# V2.net
KiCad netlist of a schematic drawn in EAGLE
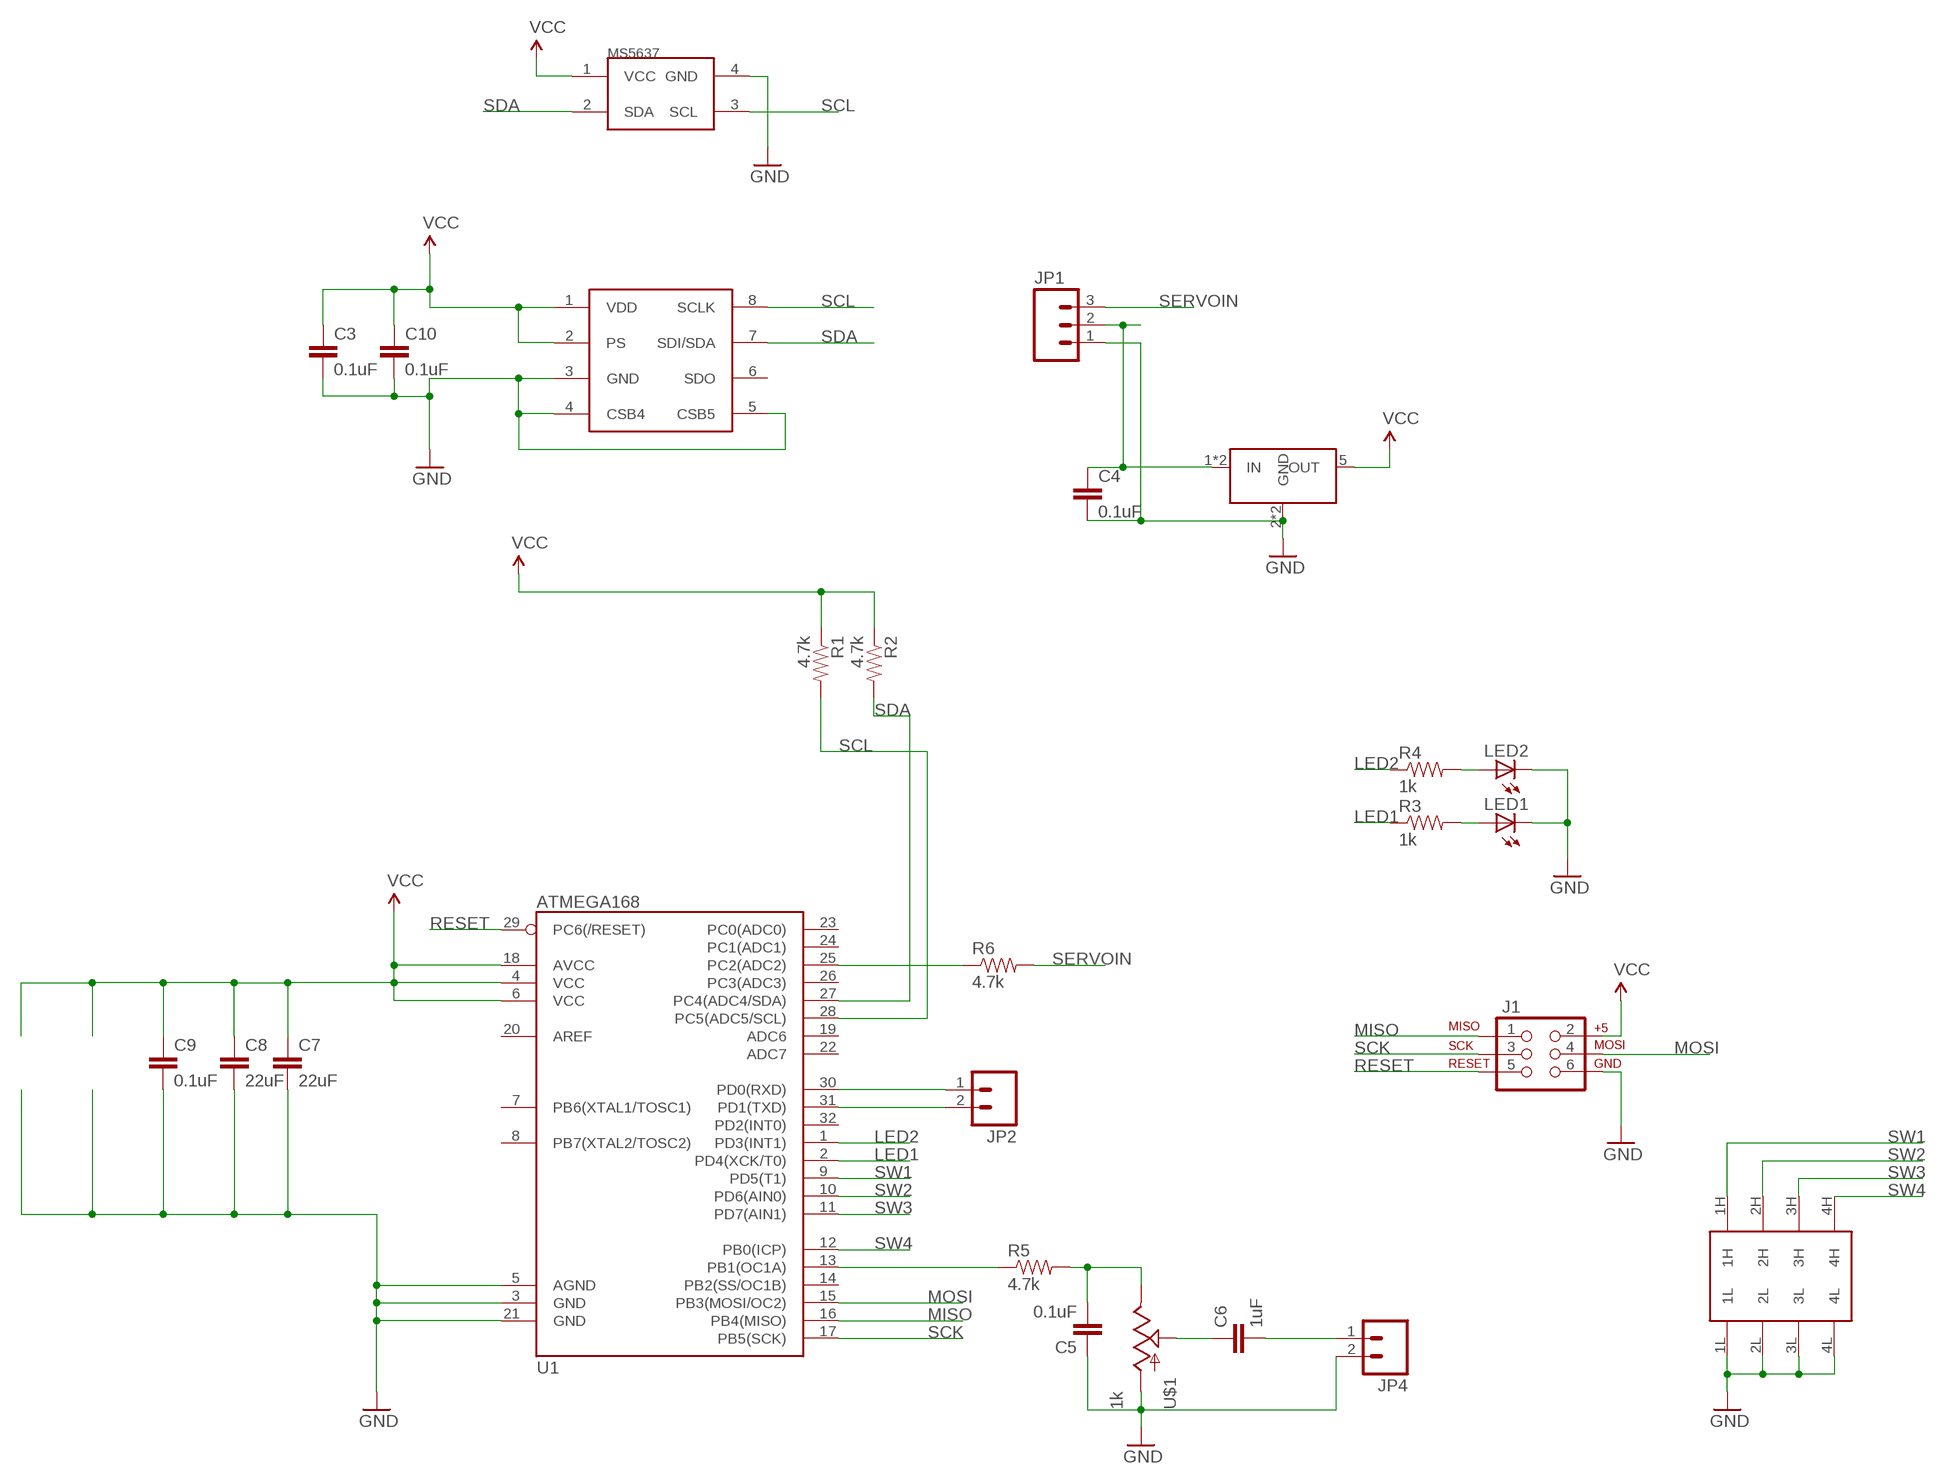
[diagram p0: schematic, sheet 1]

(export (version "E")
  (design (tool "Eeschema 10.0.6"))
  (components
    (comp (ref "C3")
      (value "0.1uF")
      (footprint "eagle-import:0603-CAP")
      (libsource (lib "eagle-import") (part "CAP0603-CAP"))
    )
    (comp (ref "C4")
      (value "0.1uF")
      (footprint "eagle-import:0603-CAP")
      (libsource (lib "eagle-import") (part "CAP0603-CAP"))
    )
    (comp (ref "C5")
      (value "0.1uF")
      (footprint "eagle-import:0603-CAP")
      (libsource (lib "eagle-import") (part "CAP0603-CAP"))
    )
    (comp (ref "C6")
      (value "1uF")
      (footprint "eagle-import:0603-CAP")
      (libsource (lib "eagle-import") (part "CAP0603-CAP"))
    )
    (comp (ref "C7")
      (value "22uF")
      (footprint "eagle-import:0805")
      (libsource (lib "eagle-import") (part "CAP0805"))
    )
    (comp (ref "C8")
      (value "22uF")
      (footprint "eagle-import:0805")
      (libsource (lib "eagle-import") (part "CAP0805"))
    )
    (comp (ref "C9")
      (value "0.1uF")
      (footprint "eagle-import:0603-CAP")
      (libsource (lib "eagle-import") (part "CAP0603-CAP"))
    )
    (comp (ref "C10")
      (value "0.1uF")
      (footprint "eagle-import:0603-CAP")
      (libsource (lib "eagle-import") (part "CAP0603-CAP"))
    )
    (comp (ref "J1")
      (value "AVR_SPI_PRG_6NS")
      (footprint "eagle-import:2X3-NS")
      (libsource (lib "eagle-import") (part "AVR_SPI_PRG_6NS"))
    )
    (comp (ref "JP1")
      (value "M03PTH")
      (footprint "eagle-import:1X03")
      (libsource (lib "eagle-import") (part "M03PTH"))
    )
    (comp (ref "JP2")
      (value "M02PTH")
      (footprint "eagle-import:1X02")
      (libsource (lib "eagle-import") (part "M02PTH"))
    )
    (comp (ref "JP4")
      (value "M02PTH")
      (footprint "eagle-import:1X02")
      (libsource (lib "eagle-import") (part "M02PTH"))
    )
    (comp (ref "LED1")
      (value "LED0603")
      (footprint "eagle-import:LED-0603")
      (libsource (lib "eagle-import") (part "LED0603"))
    )
    (comp (ref "LED2")
      (value "LED0603")
      (footprint "eagle-import:LED-0603")
      (libsource (lib "eagle-import") (part "LED0603"))
    )
    (comp (ref "R1")
      (value "4.7k")
      (footprint "eagle-import:0603-RES")
      (libsource (lib "eagle-import") (part "RESISTOR0603-RES"))
    )
    (comp (ref "R2")
      (value "4.7k")
      (footprint "eagle-import:0603-RES")
      (libsource (lib "eagle-import") (part "RESISTOR0603-RES"))
    )
    (comp (ref "R3")
      (value "1k")
      (footprint "eagle-import:0603-RES")
      (libsource (lib "eagle-import") (part "RESISTOR0603-RES"))
    )
    (comp (ref "R4")
      (value "1k")
      (footprint "eagle-import:0603-RES")
      (libsource (lib "eagle-import") (part "RESISTOR0603-RES"))
    )
    (comp (ref "R5")
      (value "4.7k")
      (footprint "eagle-import:0603-RES")
      (libsource (lib "eagle-import") (part "RESISTOR0603-RES"))
    )
    (comp (ref "R6")
      (value "4.7k")
      (footprint "eagle-import:0603-RES")
      (libsource (lib "eagle-import") (part "RESISTOR0603-RES"))
    )
    (comp (ref "U$1")
      (value "1k")
      (footprint "eagle-import:BOURNS_3306KPW")
      (libsource (lib "eagle-import") (part "POTBOURNS_3306KPW"))
    )
    (comp (ref "U$2")
      (value "MS5611")
      (footprint "eagle-import:MS5611")
      (libsource (lib "eagle-import") (part "MS5611"))
    )
    (comp (ref "U$3")
      (value "LINEAR_REGSOT23-5_TOREX")
      (footprint "eagle-import:SOT23-5")
      (libsource (lib "eagle-import") (part "LINEAR_REGSOT23-5_TOREX"))
    )
    (comp (ref "U$4")
      (value "MS5637")
      (footprint "eagle-import:MS5637")
      (libsource (lib "eagle-import") (part "MS5637"))
    )
    (comp (ref "U$5")
      (value "DIP_SWITCH")
      (footprint "eagle-import:DIPSWITCH4")
      (libsource (lib "eagle-import") (part "DIP_SWITCH"))
    )
    (comp (ref "U1")
      (value "ATMEGA168")
      (footprint "eagle-import:TQFP32-08")
      (libsource (lib "eagle-import") (part "ATMEGA168"))
    )
  )
  (nets
    (net (code "1") (name "/LED1") (class "Default")
      (node (ref "R3") (pin "1") (pinfunction "1_1") (pintype "passive"))
      (node (ref "U1") (pin "2") (pinfunction "PD4(XCK/T0)_2") (pintype "bidirectional"))
    )
    (net (code "2") (name "/LED2") (class "Default")
      (node (ref "R4") (pin "1") (pinfunction "1_1") (pintype "passive"))
      (node (ref "U1") (pin "1") (pinfunction "PD3(INT1)_1") (pintype "bidirectional"))
    )
    (net (code "3") (name "/MISO") (class "Default")
      (node (ref "J1") (pin "1") (pinfunction "1_1") (pintype "passive"))
      (node (ref "U1") (pin "16") (pinfunction "PB4(MISO)_16") (pintype "bidirectional"))
    )
    (net (code "4") (name "/MOSI") (class "Default")
      (node (ref "J1") (pin "4") (pinfunction "4_4") (pintype "passive"))
      (node (ref "U1") (pin "15") (pinfunction "PB3(MOSI/OC2)_15") (pintype "bidirectional"))
    )
    (net (code "5") (name "/RESET") (class "Default")
      (node (ref "J1") (pin "5") (pinfunction "5_5") (pintype "passive"))
      (node (ref "U1") (pin "29") (pinfunction "PC6(/RESET)_29") (pintype "bidirectional"))
    )
    (net (code "6") (name "/SCK") (class "Default")
      (node (ref "J1") (pin "3") (pinfunction "3_3") (pintype "passive"))
      (node (ref "U1") (pin "17") (pinfunction "PB5(SCK)_17") (pintype "bidirectional"))
    )
    (net (code "7") (name "/SCL") (class "Default")
      (node (ref "R1") (pin "2") (pinfunction "2_2") (pintype "passive"))
      (node (ref "U$2") (pin "8") (pinfunction "SCLK_8") (pintype "bidirectional"))
      (node (ref "U$4") (pin "3") (pinfunction "SCL_3") (pintype "bidirectional"))
      (node (ref "U1") (pin "28") (pinfunction "PC5(ADC5/SCL)_28") (pintype "bidirectional"))
    )
    (net (code "8") (name "/SDA") (class "Default")
      (node (ref "R2") (pin "2") (pinfunction "2_2") (pintype "passive"))
      (node (ref "U$2") (pin "7") (pinfunction "SDI/SDA_7") (pintype "bidirectional"))
      (node (ref "U$4") (pin "2") (pinfunction "SDA_2") (pintype "bidirectional"))
      (node (ref "U1") (pin "27") (pinfunction "PC4(ADC4/SDA)_27") (pintype "bidirectional"))
    )
    (net (code "9") (name "/SERVOIN") (class "Default")
      (node (ref "JP1") (pin "3") (pinfunction "3_3") (pintype "passive"))
      (node (ref "R6") (pin "2") (pinfunction "2_2") (pintype "passive"))
    )
    (net (code "10") (name "/SW1") (class "Default")
      (node (ref "U$5") (pin "1H") (pinfunction "1H_1H") (pintype "bidirectional"))
      (node (ref "U1") (pin "9") (pinfunction "PD5(T1)_9") (pintype "bidirectional"))
    )
    (net (code "11") (name "/SW2") (class "Default")
      (node (ref "U$5") (pin "2H") (pinfunction "2H_2H") (pintype "bidirectional"))
      (node (ref "U1") (pin "10") (pinfunction "PD6(AIN0)_10") (pintype "bidirectional"))
    )
    (net (code "12") (name "/SW3") (class "Default")
      (node (ref "U$5") (pin "3H") (pinfunction "3H_3H") (pintype "bidirectional"))
      (node (ref "U1") (pin "11") (pinfunction "PD7(AIN1)_11") (pintype "bidirectional"))
    )
    (net (code "13") (name "/SW4") (class "Default")
      (node (ref "U$5") (pin "4H") (pinfunction "4H_4H") (pintype "bidirectional"))
      (node (ref "U1") (pin "12") (pinfunction "PB0(ICP)_12") (pintype "bidirectional"))
    )
    (net (code "14") (name "GND") (class "Default")
      (node (ref "C10") (pin "2") (pinfunction "2_2") (pintype "passive"))
      (node (ref "C3") (pin "2") (pinfunction "2_2") (pintype "passive"))
      (node (ref "C4") (pin "2") (pinfunction "2_2") (pintype "passive"))
      (node (ref "C5") (pin "1") (pinfunction "1_1") (pintype "passive"))
      (node (ref "C7") (pin "2") (pinfunction "2_2") (pintype "passive"))
      (node (ref "C8") (pin "2") (pinfunction "2_2") (pintype "passive"))
      (node (ref "C9") (pin "2") (pinfunction "2_2") (pintype "passive"))
      (node (ref "J1") (pin "6") (pinfunction "6_6") (pintype "passive"))
      (node (ref "JP1") (pin "1") (pinfunction "1_1") (pintype "passive"))
      (node (ref "JP4") (pin "2") (pinfunction "2_2") (pintype "passive"))
      (node (ref "LED1") (pin "C") (pinfunction "C_C") (pintype "passive"))
      (node (ref "LED2") (pin "C") (pinfunction "C_C") (pintype "passive"))
      (node (ref "U$1") (pin "3") (pinfunction "A_3") (pintype "passive"))
      (node (ref "U$2") (pin "3") (pinfunction "GND_3") (pintype "bidirectional"))
      (node (ref "U$2") (pin "4") (pinfunction "CSB4_4") (pintype "bidirectional"))
      (node (ref "U$2") (pin "5") (pinfunction "CSB5_5") (pintype "bidirectional"))
      (node (ref "U$3") (pin "2") (pinfunction "GND_2") (pintype "power_in"))
      (node (ref "U$3") (pin "3") (pinfunction "GND_3") (pintype "power_in"))
      (node (ref "U$4") (pin "4") (pinfunction "GND_4") (pintype "bidirectional"))
      (node (ref "U$5") (pin "1L") (pinfunction "1L_1L") (pintype "bidirectional"))
      (node (ref "U$5") (pin "2L") (pinfunction "2L_2L") (pintype "bidirectional"))
      (node (ref "U$5") (pin "3L") (pinfunction "3L_3L") (pintype "bidirectional"))
      (node (ref "U$5") (pin "4L") (pinfunction "4L_4L") (pintype "bidirectional"))
      (node (ref "U1") (pin "21") (pinfunction "GND_21") (pintype "bidirectional"))
      (node (ref "U1") (pin "3") (pinfunction "GND_3") (pintype "bidirectional"))
      (node (ref "U1") (pin "5") (pinfunction "AGND_5") (pintype "bidirectional"))
    )
    (net (code "15") (name "Net-(C4-Pad1)") (class "Default")
      (node (ref "C4") (pin "1") (pinfunction "1_1") (pintype "passive"))
      (node (ref "JP1") (pin "2") (pinfunction "2_2") (pintype "passive"))
      (node (ref "U$3") (pin "1") (pinfunction "IN_1") (pintype "power_in"))
      (node (ref "U$3") (pin "4") (pinfunction "IN_4") (pintype "power_in"))
    )
    (net (code "16") (name "Net-(C6-Pad2)") (class "Default")
      (node (ref "C6") (pin "2") (pinfunction "2_2") (pintype "passive"))
      (node (ref "JP4") (pin "1") (pinfunction "1_1") (pintype "passive"))
    )
    (net (code "17") (name "Net-(LED1-PadA)") (class "Default")
      (node (ref "LED1") (pin "A") (pinfunction "A_A") (pintype "passive"))
      (node (ref "R3") (pin "2") (pinfunction "2_2") (pintype "passive"))
    )
    (net (code "18") (name "Net-(LED2-PadA)") (class "Default")
      (node (ref "LED2") (pin "A") (pinfunction "A_A") (pintype "passive"))
      (node (ref "R4") (pin "2") (pinfunction "2_2") (pintype "passive"))
    )
    (net (code "19") (name "Net-(U$1-E)") (class "Default")
      (node (ref "C5") (pin "2") (pinfunction "2_2") (pintype "passive"))
      (node (ref "R5") (pin "2") (pinfunction "2_2") (pintype "passive"))
      (node (ref "U$1") (pin "1") (pinfunction "E_1") (pintype "passive"))
    )
    (net (code "20") (name "Net-(U$1-S)") (class "Default")
      (node (ref "C6") (pin "1") (pinfunction "1_1") (pintype "passive"))
      (node (ref "U$1") (pin "2") (pinfunction "S_2") (pintype "passive"))
    )
    (net (code "21") (name "Net-(U1-PB1(OC1A))") (class "Default")
      (node (ref "R5") (pin "1") (pinfunction "1_1") (pintype "passive"))
      (node (ref "U1") (pin "13") (pinfunction "PB1(OC1A)_13") (pintype "bidirectional"))
    )
    (net (code "22") (name "Net-(U1-PC2(ADC2))") (class "Default")
      (node (ref "R6") (pin "1") (pinfunction "1_1") (pintype "passive"))
      (node (ref "U1") (pin "25") (pinfunction "PC2(ADC2)_25") (pintype "bidirectional"))
    )
    (net (code "23") (name "Net-(U1-PD0(RXD))") (class "Default")
      (node (ref "JP2") (pin "1") (pinfunction "1_1") (pintype "passive"))
      (node (ref "U1") (pin "30") (pinfunction "PD0(RXD)_30") (pintype "bidirectional"))
    )
    (net (code "24") (name "Net-(U1-PD1(TXD))") (class "Default")
      (node (ref "JP2") (pin "2") (pinfunction "2_2") (pintype "passive"))
      (node (ref "U1") (pin "31") (pinfunction "PD1(TXD)_31") (pintype "bidirectional"))
    )
    (net (code "25") (name "VCC") (class "Default")
      (node (ref "C10") (pin "1") (pinfunction "1_1") (pintype "passive"))
      (node (ref "C3") (pin "1") (pinfunction "1_1") (pintype "passive"))
      (node (ref "C7") (pin "1") (pinfunction "1_1") (pintype "passive"))
      (node (ref "C8") (pin "1") (pinfunction "1_1") (pintype "passive"))
      (node (ref "C9") (pin "1") (pinfunction "1_1") (pintype "passive"))
      (node (ref "J1") (pin "2") (pinfunction "2_2") (pintype "passive"))
      (node (ref "R1") (pin "1") (pinfunction "1_1") (pintype "passive"))
      (node (ref "R2") (pin "1") (pinfunction "1_1") (pintype "passive"))
      (node (ref "U$2") (pin "1") (pinfunction "VDD_1") (pintype "bidirectional"))
      (node (ref "U$2") (pin "2") (pinfunction "PS_2") (pintype "bidirectional"))
      (node (ref "U$3") (pin "5") (pinfunction "OUT_5") (pintype "power_in"))
      (node (ref "U$4") (pin "1") (pinfunction "VCC_1") (pintype "bidirectional"))
      (node (ref "U1") (pin "18") (pinfunction "AVCC_18") (pintype "bidirectional"))
      (node (ref "U1") (pin "4") (pinfunction "VCC_4") (pintype "bidirectional"))
      (node (ref "U1") (pin "6") (pinfunction "VCC_6") (pintype "bidirectional"))
    )
    (net (code "26") (name "unconnected-(U$2-SDO-Pad6)") (class "Default")
      (node (ref "U$2") (pin "6") (pinfunction "SDO_6") (pintype "bidirectional"))
    )
    (net (code "27") (name "unconnected-(U1-ADC6-Pad19)") (class "Default")
      (node (ref "U1") (pin "19") (pinfunction "ADC6_19") (pintype "bidirectional"))
    )
    (net (code "28") (name "unconnected-(U1-ADC7-Pad22)") (class "Default")
      (node (ref "U1") (pin "22") (pinfunction "ADC7_22") (pintype "bidirectional"))
    )
    (net (code "29") (name "unconnected-(U1-AREF-Pad20)") (class "Default")
      (node (ref "U1") (pin "20") (pinfunction "AREF_20") (pintype "bidirectional"))
    )
    (net (code "30") (name "unconnected-(U1-PB2(SS{slash}OC1B)-Pad14)") (class "Default")
      (node (ref "U1") (pin "14") (pinfunction "PB2(SS/OC1B)_14") (pintype "bidirectional"))
    )
    (net (code "31") (name "unconnected-(U1-PB6(XTAL1{slash}TOSC1)-Pad7)") (class "Default")
      (node (ref "U1") (pin "7") (pinfunction "PB6(XTAL1/TOSC1)_7") (pintype "bidirectional"))
    )
    (net (code "32") (name "unconnected-(U1-PB7(XTAL2{slash}TOSC2)-Pad8)") (class "Default")
      (node (ref "U1") (pin "8") (pinfunction "PB7(XTAL2/TOSC2)_8") (pintype "bidirectional"))
    )
    (net (code "33") (name "unconnected-(U1-PC0(ADC0)-Pad23)") (class "Default")
      (node (ref "U1") (pin "23") (pinfunction "PC0(ADC0)_23") (pintype "bidirectional"))
    )
    (net (code "34") (name "unconnected-(U1-PC1(ADC1)-Pad24)") (class "Default")
      (node (ref "U1") (pin "24") (pinfunction "PC1(ADC1)_24") (pintype "bidirectional"))
    )
    (net (code "35") (name "unconnected-(U1-PC3(ADC3)-Pad26)") (class "Default")
      (node (ref "U1") (pin "26") (pinfunction "PC3(ADC3)_26") (pintype "bidirectional"))
    )
    (net (code "36") (name "unconnected-(U1-PD2(INT0)-Pad32)") (class "Default")
      (node (ref "U1") (pin "32") (pinfunction "PD2(INT0)_32") (pintype "bidirectional"))
    )
  )
)
